# PulseChord.net
KiCad netlist of a schematic drawn in EAGLE
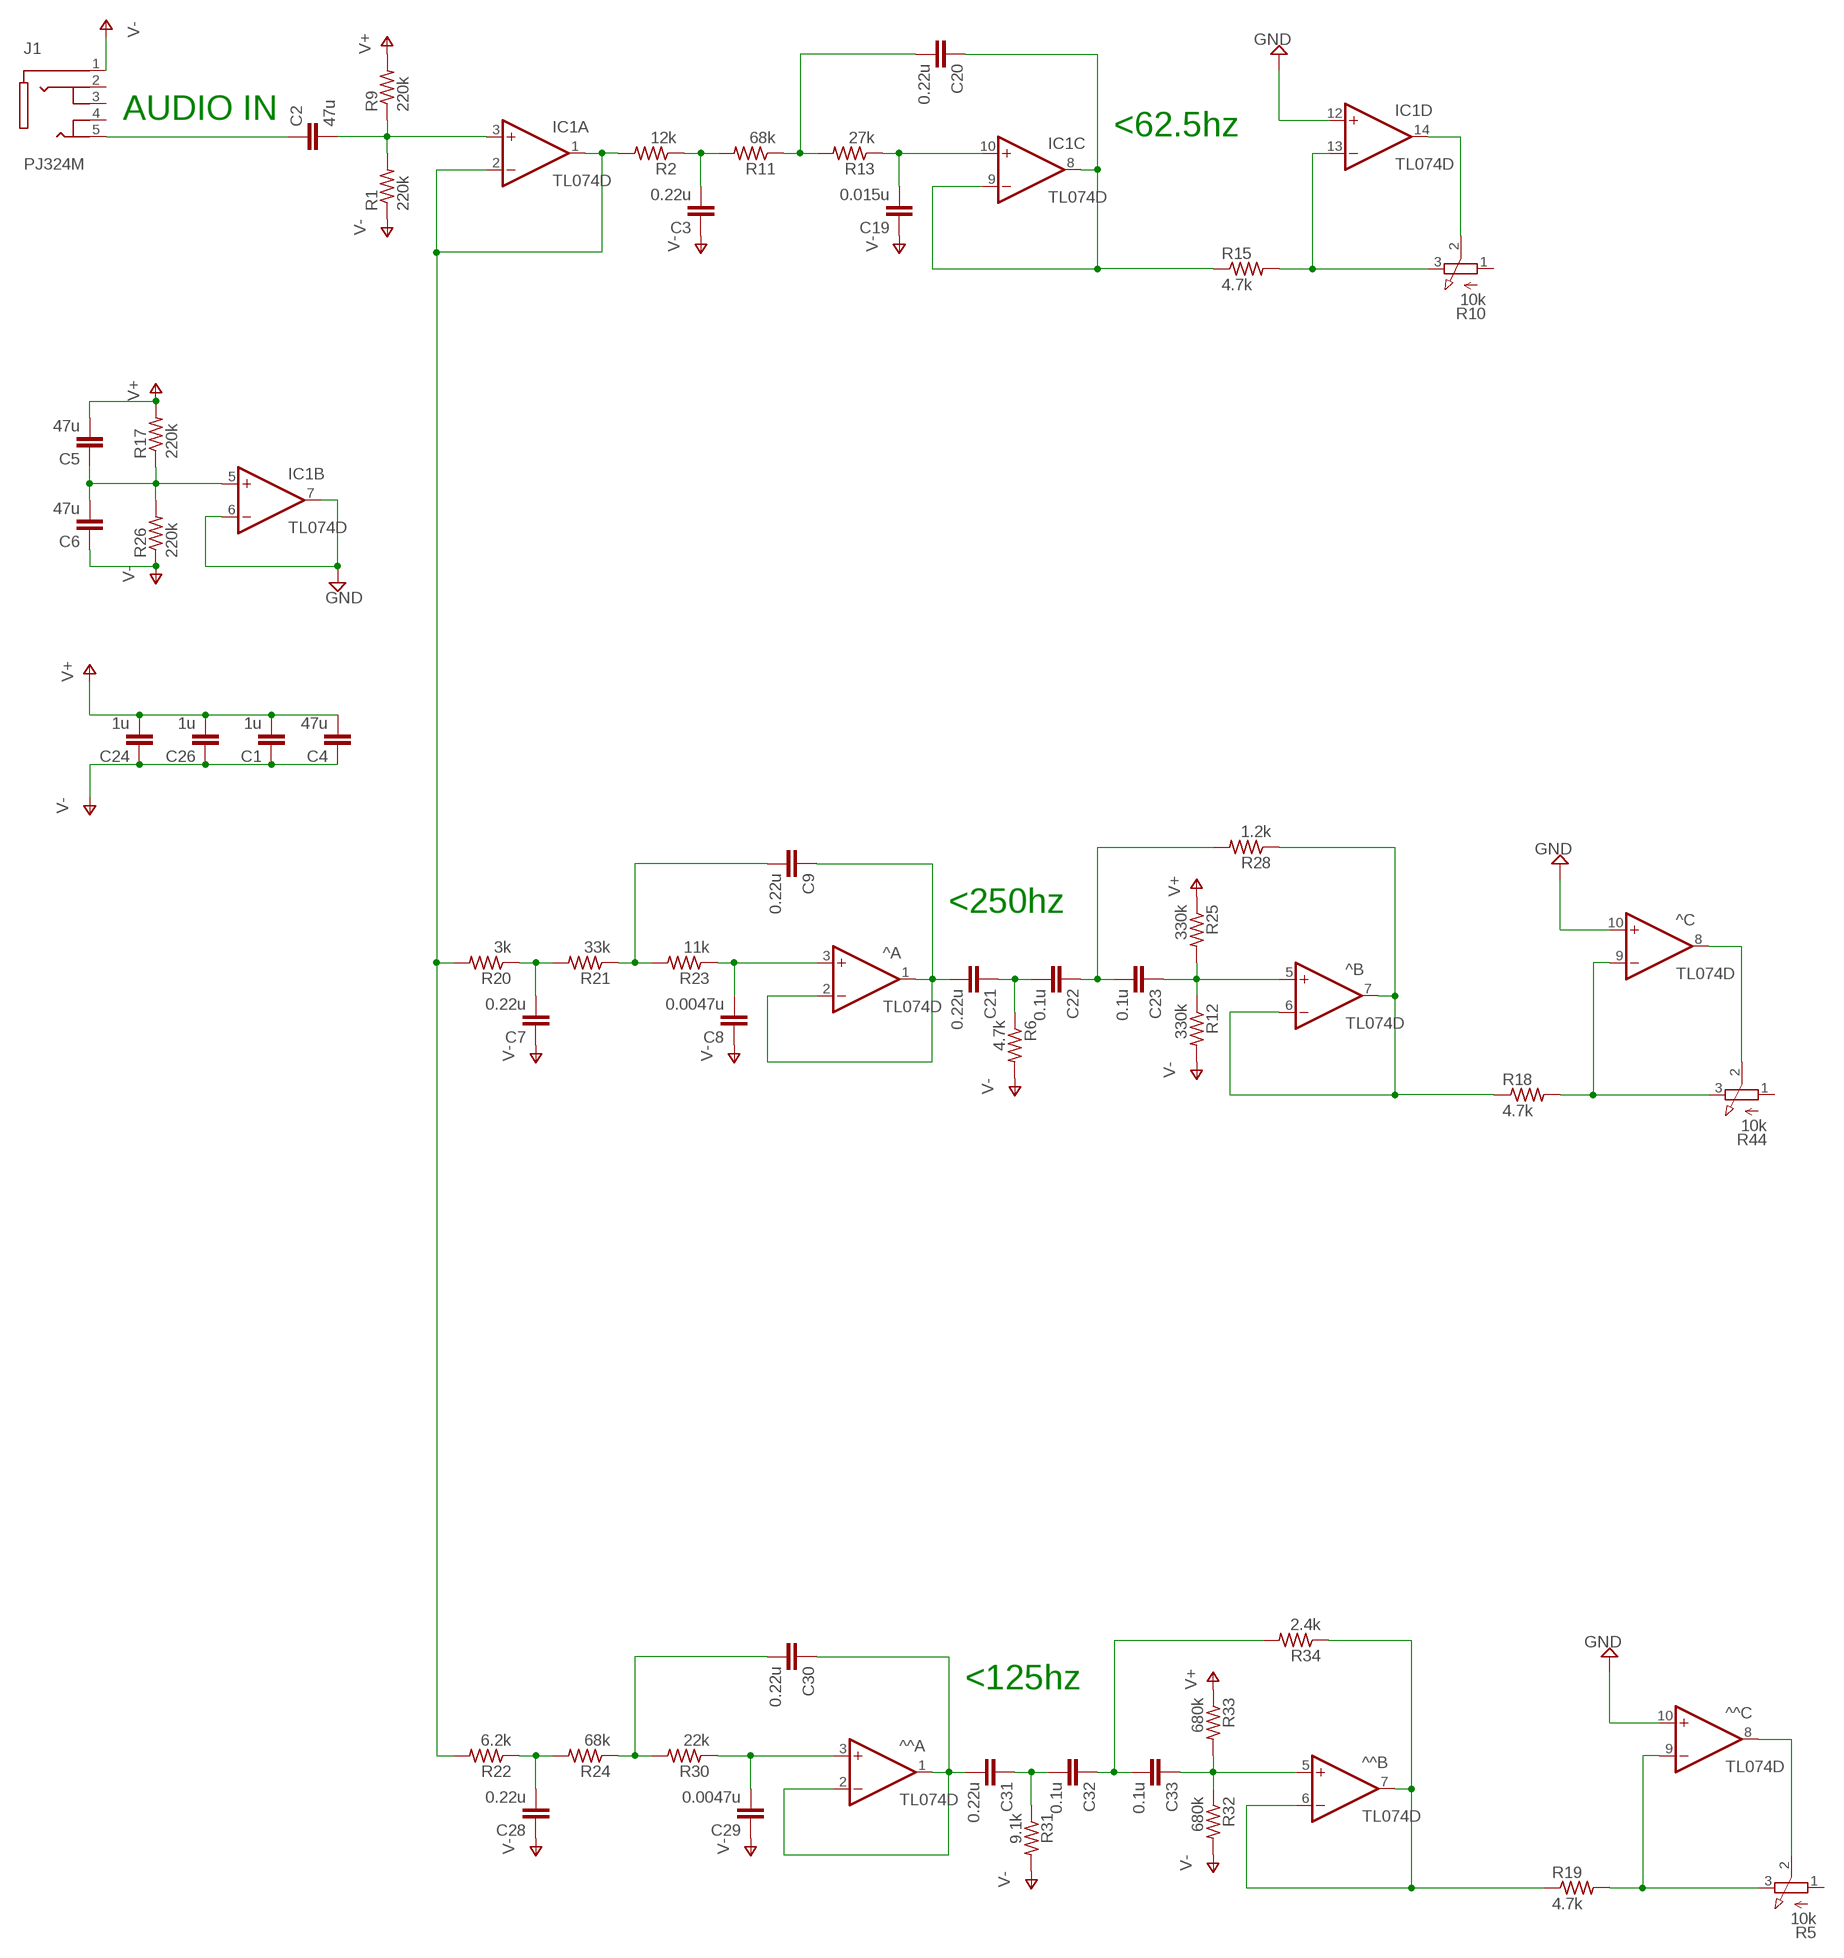
[diagram p0: schematic, sheet 1]

(export (version "E")
  (design (tool "Eeschema 10.0.6"))
  (components
    (comp (ref "C1")
      (value "1u")
      (footprint "eagle-import:C0603")
      (libsource (lib "eagle-import") (part "C-EUC0603"))
    )
    (comp (ref "C2")
      (value "47u")
      (footprint "eagle-import:C0603")
      (libsource (lib "eagle-import") (part "C-EUC0603"))
    )
    (comp (ref "C3")
      (value "0.22u")
      (footprint "eagle-import:C0603")
      (libsource (lib "eagle-import") (part "C-EUC0603"))
    )
    (comp (ref "C4")
      (value "47u")
      (footprint "eagle-import:C0603")
      (libsource (lib "eagle-import") (part "C-EUC0603"))
    )
    (comp (ref "C5")
      (value "47u")
      (footprint "eagle-import:C0603")
      (libsource (lib "eagle-import") (part "C-EUC0603"))
    )
    (comp (ref "C6")
      (value "47u")
      (footprint "eagle-import:C0603")
      (libsource (lib "eagle-import") (part "C-EUC0603"))
    )
    (comp (ref "C7")
      (value "0.22u")
      (footprint "eagle-import:C0603")
      (libsource (lib "eagle-import") (part "C-EUC0603"))
    )
    (comp (ref "C8")
      (value "0.0047u")
      (footprint "eagle-import:C0603")
      (libsource (lib "eagle-import") (part "C-EUC0603"))
    )
    (comp (ref "C9")
      (value "0.22u")
      (footprint "eagle-import:C0603")
      (libsource (lib "eagle-import") (part "C-EUC0603"))
    )
    (comp (ref "C19")
      (value "0.015u")
      (footprint "eagle-import:C0603")
      (libsource (lib "eagle-import") (part "C-EUC0603"))
    )
    (comp (ref "C20")
      (value "0.22u")
      (footprint "eagle-import:C0603")
      (libsource (lib "eagle-import") (part "C-EUC0603"))
    )
    (comp (ref "C21")
      (value "0.22u")
      (footprint "eagle-import:C0603")
      (libsource (lib "eagle-import") (part "C-EUC0603"))
    )
    (comp (ref "C22")
      (value "0.1u")
      (footprint "eagle-import:C0603")
      (libsource (lib "eagle-import") (part "C-EUC0603"))
    )
    (comp (ref "C23")
      (value "0.1u")
      (footprint "eagle-import:C0603")
      (libsource (lib "eagle-import") (part "C-EUC0603"))
    )
    (comp (ref "C24")
      (value "1u")
      (footprint "eagle-import:C0603")
      (libsource (lib "eagle-import") (part "C-EUC0603"))
    )
    (comp (ref "C26")
      (value "1u")
      (footprint "eagle-import:C0603")
      (libsource (lib "eagle-import") (part "C-EUC0603"))
    )
    (comp (ref "C28")
      (value "0.22u")
      (footprint "eagle-import:C0603")
      (libsource (lib "eagle-import") (part "C-EUC0603"))
    )
    (comp (ref "C29")
      (value "0.0047u")
      (footprint "eagle-import:C0603")
      (libsource (lib "eagle-import") (part "C-EUC0603"))
    )
    (comp (ref "C30")
      (value "0.22u")
      (footprint "eagle-import:C0603")
      (libsource (lib "eagle-import") (part "C-EUC0603"))
    )
    (comp (ref "C31")
      (value "0.22u")
      (footprint "eagle-import:C0603")
      (libsource (lib "eagle-import") (part "C-EUC0603"))
    )
    (comp (ref "C32")
      (value "0.1u")
      (footprint "eagle-import:C0603")
      (libsource (lib "eagle-import") (part "C-EUC0603"))
    )
    (comp (ref "C33")
      (value "0.1u")
      (footprint "eagle-import:C0603")
      (libsource (lib "eagle-import") (part "C-EUC0603"))
    )
    (comp (ref "IC1")
      (value "TL074D")
      (footprint "eagle-import:SO14")
      (libsource (lib "eagle-import") (part "TL074D"))
    )
    (comp (ref "J1")
      (value "PJ324M")
      (footprint "eagle-import:WENZHOU_PJ324M")
      (fields (field (name "MF") "Wenzhou QingPu Electronics Co.Ltd"))
      (libsource (lib "eagle-import") (part "PJ324M"))
    )
    (comp (ref "R1")
      (value "220k")
      (footprint "eagle-import:R0603")
      (libsource (lib "eagle-import") (part "R-US_R0603"))
    )
    (comp (ref "R2")
      (value "12k")
      (footprint "eagle-import:R0603")
      (libsource (lib "eagle-import") (part "R-US_R0603"))
    )
    (comp (ref "R5")
      (value "10k")
      (footprint "eagle-import:3RP_1610N")
      (libsource (lib "eagle-import") (part "3RP/1610N"))
    )
    (comp (ref "R6")
      (value "4.7k")
      (footprint "eagle-import:R0603")
      (libsource (lib "eagle-import") (part "R-US_R0603"))
    )
    (comp (ref "R9")
      (value "220k")
      (footprint "eagle-import:R0603")
      (libsource (lib "eagle-import") (part "R-US_R0603"))
    )
    (comp (ref "R10")
      (value "10k")
      (footprint "eagle-import:3RP_1610N")
      (libsource (lib "eagle-import") (part "3RP/1610N"))
    )
    (comp (ref "R11")
      (value "68k")
      (footprint "eagle-import:R0603")
      (libsource (lib "eagle-import") (part "R-US_R0603"))
    )
    (comp (ref "R12")
      (value "330k")
      (footprint "eagle-import:R0603")
      (libsource (lib "eagle-import") (part "R-US_R0603"))
    )
    (comp (ref "R13")
      (value "27k")
      (footprint "eagle-import:R0603")
      (libsource (lib "eagle-import") (part "R-US_R0603"))
    )
    (comp (ref "R15")
      (value "4.7k")
      (footprint "eagle-import:R0603")
      (libsource (lib "eagle-import") (part "R-US_R0603"))
    )
    (comp (ref "R17")
      (value "220k")
      (footprint "eagle-import:R0603")
      (libsource (lib "eagle-import") (part "R-US_R0603"))
    )
    (comp (ref "R18")
      (value "4.7k")
      (footprint "eagle-import:R0603")
      (libsource (lib "eagle-import") (part "R-US_R0603"))
    )
    (comp (ref "R19")
      (value "4.7k")
      (footprint "eagle-import:R0603")
      (libsource (lib "eagle-import") (part "R-US_R0603"))
    )
    (comp (ref "R20")
      (value "3k")
      (footprint "eagle-import:R0603")
      (libsource (lib "eagle-import") (part "R-US_R0603"))
    )
    (comp (ref "R21")
      (value "33k")
      (footprint "eagle-import:R0603")
      (libsource (lib "eagle-import") (part "R-US_R0603"))
    )
    (comp (ref "R22")
      (value "6.2k")
      (footprint "eagle-import:R0603")
      (libsource (lib "eagle-import") (part "R-US_R0603"))
    )
    (comp (ref "R23")
      (value "11k")
      (footprint "eagle-import:R0603")
      (libsource (lib "eagle-import") (part "R-US_R0603"))
    )
    (comp (ref "R24")
      (value "68k")
      (footprint "eagle-import:R0603")
      (libsource (lib "eagle-import") (part "R-US_R0603"))
    )
    (comp (ref "R25")
      (value "330k")
      (footprint "eagle-import:R0603")
      (libsource (lib "eagle-import") (part "R-US_R0603"))
    )
    (comp (ref "R26")
      (value "220k")
      (footprint "eagle-import:R0603")
      (libsource (lib "eagle-import") (part "R-US_R0603"))
    )
    (comp (ref "R28")
      (value "1.2k")
      (footprint "eagle-import:R0603")
      (libsource (lib "eagle-import") (part "R-US_R0603"))
    )
    (comp (ref "R30")
      (value "22k")
      (footprint "eagle-import:R0603")
      (libsource (lib "eagle-import") (part "R-US_R0603"))
    )
    (comp (ref "R31")
      (value "9.1k")
      (footprint "eagle-import:R0603")
      (libsource (lib "eagle-import") (part "R-US_R0603"))
    )
    (comp (ref "R32")
      (value "680k")
      (footprint "eagle-import:R0603")
      (libsource (lib "eagle-import") (part "R-US_R0603"))
    )
    (comp (ref "R33")
      (value "680k")
      (footprint "eagle-import:R0603")
      (libsource (lib "eagle-import") (part "R-US_R0603"))
    )
    (comp (ref "R34")
      (value "2.4k")
      (footprint "eagle-import:R0603")
      (libsource (lib "eagle-import") (part "R-US_R0603"))
    )
    (comp (ref "R44")
      (value "10k")
      (footprint "eagle-import:3RP_1610N")
      (libsource (lib "eagle-import") (part "3RP/1610N"))
    )
    (comp (ref "^")
      (value "TL074D")
      (footprint "eagle-import:SO14")
      (libsource (lib "eagle-import") (part "TL074D"))
    )
    (comp (ref "^^")
      (value "TL074D")
      (footprint "eagle-import:SO14")
      (libsource (lib "eagle-import") (part "TL074D"))
    )
  )
  (nets
    (net (code "1") (name "GND") (class "Default")
      (node (ref "IC1") (pin "12") (pinfunction "+IN_12") (pintype "input"))
      (node (ref "IC1") (pin "6") (pinfunction "-IN_6") (pintype "input"))
      (node (ref "IC1") (pin "7") (pinfunction "OUT_7") (pintype "output"))
      (node (ref "^") (pin "10") (pinfunction "+IN_10") (pintype "input"))
      (node (ref "^^") (pin "10") (pinfunction "+IN_10") (pintype "input"))
    )
    (net (code "2") (name "Net-(C3-Pad2)") (class "Default")
      (node (ref "C3") (pin "2") (pinfunction "2_2") (pintype "passive"))
      (node (ref "R11") (pin "2") (pinfunction "2_2") (pintype "passive"))
      (node (ref "R2") (pin "1") (pinfunction "1_1") (pintype "passive"))
    )
    (net (code "3") (name "Net-(C7-Pad2)") (class "Default")
      (node (ref "C7") (pin "2") (pinfunction "2_2") (pintype "passive"))
      (node (ref "R20") (pin "1") (pinfunction "1_1") (pintype "passive"))
      (node (ref "R21") (pin "2") (pinfunction "2_2") (pintype "passive"))
    )
    (net (code "4") (name "Net-(C9-Pad2)") (class "Default")
      (node (ref "C9") (pin "2") (pinfunction "2_2") (pintype "passive"))
      (node (ref "R21") (pin "1") (pinfunction "1_1") (pintype "passive"))
      (node (ref "R23") (pin "2") (pinfunction "2_2") (pintype "passive"))
    )
    (net (code "5") (name "Net-(C20-Pad2)") (class "Default")
      (node (ref "C20") (pin "2") (pinfunction "2_2") (pintype "passive"))
      (node (ref "R11") (pin "1") (pinfunction "1_1") (pintype "passive"))
      (node (ref "R13") (pin "2") (pinfunction "2_2") (pintype "passive"))
    )
    (net (code "6") (name "Net-(C21-Pad1)") (class "Default")
      (node (ref "C21") (pin "1") (pinfunction "1_1") (pintype "passive"))
      (node (ref "C22") (pin "2") (pinfunction "2_2") (pintype "passive"))
      (node (ref "R6") (pin "1") (pinfunction "1_1") (pintype "passive"))
    )
    (net (code "7") (name "Net-(C22-Pad1)") (class "Default")
      (node (ref "C22") (pin "1") (pinfunction "1_1") (pintype "passive"))
      (node (ref "C23") (pin "2") (pinfunction "2_2") (pintype "passive"))
      (node (ref "R28") (pin "2") (pinfunction "2_2") (pintype "passive"))
    )
    (net (code "8") (name "Net-(C28-Pad2)") (class "Default")
      (node (ref "C28") (pin "2") (pinfunction "2_2") (pintype "passive"))
      (node (ref "R22") (pin "1") (pinfunction "1_1") (pintype "passive"))
      (node (ref "R24") (pin "2") (pinfunction "2_2") (pintype "passive"))
    )
    (net (code "9") (name "Net-(C30-Pad2)") (class "Default")
      (node (ref "C30") (pin "2") (pinfunction "2_2") (pintype "passive"))
      (node (ref "R24") (pin "1") (pinfunction "1_1") (pintype "passive"))
      (node (ref "R30") (pin "2") (pinfunction "2_2") (pintype "passive"))
    )
    (net (code "10") (name "Net-(C31-Pad1)") (class "Default")
      (node (ref "C31") (pin "1") (pinfunction "1_1") (pintype "passive"))
      (node (ref "C32") (pin "2") (pinfunction "2_2") (pintype "passive"))
      (node (ref "R31") (pin "1") (pinfunction "1_1") (pintype "passive"))
    )
    (net (code "11") (name "Net-(C32-Pad1)") (class "Default")
      (node (ref "C32") (pin "1") (pinfunction "1_1") (pintype "passive"))
      (node (ref "C33") (pin "2") (pinfunction "2_2") (pintype "passive"))
      (node (ref "R34") (pin "2") (pinfunction "2_2") (pintype "passive"))
    )
    (net (code "12") (name "Net-(IC1A-+IN)") (class "Default")
      (node (ref "C2") (pin "2") (pinfunction "2_2") (pintype "passive"))
      (node (ref "IC1") (pin "3") (pinfunction "+IN_3") (pintype "input"))
      (node (ref "R1") (pin "2") (pinfunction "2_2") (pintype "passive"))
      (node (ref "R9") (pin "1") (pinfunction "1_1") (pintype "passive"))
    )
    (net (code "13") (name "Net-(IC1A--IN)") (class "Default")
      (node (ref "IC1") (pin "1") (pinfunction "OUT_1") (pintype "output"))
      (node (ref "IC1") (pin "2") (pinfunction "-IN_2") (pintype "input"))
      (node (ref "R2") (pin "2") (pinfunction "2_2") (pintype "passive"))
      (node (ref "R20") (pin "2") (pinfunction "2_2") (pintype "passive"))
      (node (ref "R22") (pin "2") (pinfunction "2_2") (pintype "passive"))
    )
    (net (code "14") (name "Net-(IC1B-+IN)") (class "Default")
      (node (ref "C5") (pin "1") (pinfunction "1_1") (pintype "passive"))
      (node (ref "C6") (pin "2") (pinfunction "2_2") (pintype "passive"))
      (node (ref "IC1") (pin "5") (pinfunction "+IN_5") (pintype "input"))
      (node (ref "R17") (pin "1") (pinfunction "1_1") (pintype "passive"))
      (node (ref "R26") (pin "2") (pinfunction "2_2") (pintype "passive"))
    )
    (net (code "15") (name "Net-(IC1C-+IN)") (class "Default")
      (node (ref "C19") (pin "2") (pinfunction "2_2") (pintype "passive"))
      (node (ref "IC1") (pin "10") (pinfunction "+IN_10") (pintype "input"))
      (node (ref "R13") (pin "1") (pinfunction "1_1") (pintype "passive"))
    )
    (net (code "16") (name "Net-(IC1C--IN)") (class "Default")
      (node (ref "C20") (pin "1") (pinfunction "1_1") (pintype "passive"))
      (node (ref "IC1") (pin "8") (pinfunction "OUT_8") (pintype "output"))
      (node (ref "IC1") (pin "9") (pinfunction "-IN_9") (pintype "input"))
      (node (ref "R15") (pin "1") (pinfunction "1_1") (pintype "passive"))
    )
    (net (code "17") (name "Net-(IC1D--IN)") (class "Default")
      (node (ref "IC1") (pin "13") (pinfunction "-IN_13") (pintype "input"))
      (node (ref "R10") (pin "3") (pinfunction "E_3") (pintype "passive"))
      (node (ref "R15") (pin "2") (pinfunction "2_2") (pintype "passive"))
    )
    (net (code "18") (name "Net-(IC1D-OUT)") (class "Default")
      (node (ref "IC1") (pin "14") (pinfunction "OUT_14") (pintype "output"))
      (node (ref "R10") (pin "2") (pinfunction "S_2") (pintype "passive"))
    )
    (net (code "19") (name "Net-(J1-TIP_2)") (class "Default")
      (node (ref "C2") (pin "1") (pinfunction "1_1") (pintype "passive"))
      (node (ref "J1") (pin "5") (pinfunction "TIP_2_5") (pintype "passive"))
    )
    (net (code "20") (name "Net-(R5-E)") (class "Default")
      (node (ref "R19") (pin "2") (pinfunction "2_2") (pintype "passive"))
      (node (ref "R5") (pin "3") (pinfunction "E_3") (pintype "passive"))
      (node (ref "^^") (pin "9") (pinfunction "-IN_9") (pintype "input"))
    )
    (net (code "21") (name "Net-(R5-S)") (class "Default")
      (node (ref "R5") (pin "2") (pinfunction "S_2") (pintype "passive"))
      (node (ref "^^") (pin "8") (pinfunction "OUT_8") (pintype "output"))
    )
    (net (code "22") (name "Net-(R44-E)") (class "Default")
      (node (ref "R18") (pin "2") (pinfunction "2_2") (pintype "passive"))
      (node (ref "R44") (pin "3") (pinfunction "E_3") (pintype "passive"))
      (node (ref "^") (pin "9") (pinfunction "-IN_9") (pintype "input"))
    )
    (net (code "23") (name "Net-(R44-S)") (class "Default")
      (node (ref "R44") (pin "2") (pinfunction "S_2") (pintype "passive"))
      (node (ref "^") (pin "8") (pinfunction "OUT_8") (pintype "output"))
    )
    (net (code "24") (name "Net-(^A-+IN)") (class "Default")
      (node (ref "C8") (pin "2") (pinfunction "2_2") (pintype "passive"))
      (node (ref "R23") (pin "1") (pinfunction "1_1") (pintype "passive"))
      (node (ref "^") (pin "3") (pinfunction "+IN_3") (pintype "input"))
    )
    (net (code "25") (name "Net-(^A--IN)") (class "Default")
      (node (ref "C21") (pin "2") (pinfunction "2_2") (pintype "passive"))
      (node (ref "C9") (pin "1") (pinfunction "1_1") (pintype "passive"))
      (node (ref "^") (pin "1") (pinfunction "OUT_1") (pintype "output"))
      (node (ref "^") (pin "2") (pinfunction "-IN_2") (pintype "input"))
    )
    (net (code "26") (name "Net-(^B-+IN)") (class "Default")
      (node (ref "C23") (pin "1") (pinfunction "1_1") (pintype "passive"))
      (node (ref "R12") (pin "1") (pinfunction "1_1") (pintype "passive"))
      (node (ref "R25") (pin "2") (pinfunction "2_2") (pintype "passive"))
      (node (ref "^") (pin "5") (pinfunction "+IN_5") (pintype "input"))
    )
    (net (code "27") (name "Net-(^B--IN)") (class "Default")
      (node (ref "R18") (pin "1") (pinfunction "1_1") (pintype "passive"))
      (node (ref "R28") (pin "1") (pinfunction "1_1") (pintype "passive"))
      (node (ref "^") (pin "6") (pinfunction "-IN_6") (pintype "input"))
      (node (ref "^") (pin "7") (pinfunction "OUT_7") (pintype "output"))
    )
    (net (code "28") (name "Net-(^^A-+IN)") (class "Default")
      (node (ref "C29") (pin "2") (pinfunction "2_2") (pintype "passive"))
      (node (ref "R30") (pin "1") (pinfunction "1_1") (pintype "passive"))
      (node (ref "^^") (pin "3") (pinfunction "+IN_3") (pintype "input"))
    )
    (net (code "29") (name "Net-(^^A--IN)") (class "Default")
      (node (ref "C30") (pin "1") (pinfunction "1_1") (pintype "passive"))
      (node (ref "C31") (pin "2") (pinfunction "2_2") (pintype "passive"))
      (node (ref "^^") (pin "1") (pinfunction "OUT_1") (pintype "output"))
      (node (ref "^^") (pin "2") (pinfunction "-IN_2") (pintype "input"))
    )
    (net (code "30") (name "Net-(^^B-+IN)") (class "Default")
      (node (ref "C33") (pin "1") (pinfunction "1_1") (pintype "passive"))
      (node (ref "R32") (pin "1") (pinfunction "1_1") (pintype "passive"))
      (node (ref "R33") (pin "2") (pinfunction "2_2") (pintype "passive"))
      (node (ref "^^") (pin "5") (pinfunction "+IN_5") (pintype "input"))
    )
    (net (code "31") (name "Net-(^^B--IN)") (class "Default")
      (node (ref "R19") (pin "1") (pinfunction "1_1") (pintype "passive"))
      (node (ref "R34") (pin "1") (pinfunction "1_1") (pintype "passive"))
      (node (ref "^^") (pin "6") (pinfunction "-IN_6") (pintype "input"))
      (node (ref "^^") (pin "7") (pinfunction "OUT_7") (pintype "output"))
    )
    (net (code "32") (name "V+") (class "Default")
      (node (ref "C1") (pin "2") (pinfunction "2_2") (pintype "passive"))
      (node (ref "C24") (pin "2") (pinfunction "2_2") (pintype "passive"))
      (node (ref "C26") (pin "2") (pinfunction "2_2") (pintype "passive"))
      (node (ref "C4") (pin "2") (pinfunction "2_2") (pintype "passive"))
      (node (ref "C5") (pin "2") (pinfunction "2_2") (pintype "passive"))
      (node (ref "R17") (pin "2") (pinfunction "2_2") (pintype "passive"))
      (node (ref "R25") (pin "1") (pinfunction "1_1") (pintype "passive"))
      (node (ref "R33") (pin "1") (pinfunction "1_1") (pintype "passive"))
      (node (ref "R9") (pin "2") (pinfunction "2_2") (pintype "passive"))
    )
    (net (code "33") (name "V-") (class "Default")
      (node (ref "C1") (pin "1") (pinfunction "1_1") (pintype "passive"))
      (node (ref "C19") (pin "1") (pinfunction "1_1") (pintype "passive"))
      (node (ref "C24") (pin "1") (pinfunction "1_1") (pintype "passive"))
      (node (ref "C26") (pin "1") (pinfunction "1_1") (pintype "passive"))
      (node (ref "C28") (pin "1") (pinfunction "1_1") (pintype "passive"))
      (node (ref "C29") (pin "1") (pinfunction "1_1") (pintype "passive"))
      (node (ref "C3") (pin "1") (pinfunction "1_1") (pintype "passive"))
      (node (ref "C4") (pin "1") (pinfunction "1_1") (pintype "passive"))
      (node (ref "C6") (pin "1") (pinfunction "1_1") (pintype "passive"))
      (node (ref "C7") (pin "1") (pinfunction "1_1") (pintype "passive"))
      (node (ref "C8") (pin "1") (pinfunction "1_1") (pintype "passive"))
      (node (ref "J1") (pin "1") (pinfunction "SLEEVE_1") (pintype "passive"))
      (node (ref "R1") (pin "1") (pinfunction "1_1") (pintype "passive"))
      (node (ref "R12") (pin "2") (pinfunction "2_2") (pintype "passive"))
      (node (ref "R26") (pin "1") (pinfunction "1_1") (pintype "passive"))
      (node (ref "R31") (pin "2") (pinfunction "2_2") (pintype "passive"))
      (node (ref "R32") (pin "2") (pinfunction "2_2") (pintype "passive"))
      (node (ref "R6") (pin "2") (pinfunction "2_2") (pintype "passive"))
    )
    (net (code "34") (name "unconnected-(J1-RING_1-Pad2)") (class "Default")
      (node (ref "J1") (pin "2") (pinfunction "RING_1_2") (pintype "passive"))
    )
    (net (code "35") (name "unconnected-(J1-RING_2-Pad3)") (class "Default")
      (node (ref "J1") (pin "3") (pinfunction "RING_2_3") (pintype "passive"))
    )
    (net (code "36") (name "unconnected-(J1-TIP_1-Pad4)") (class "Default")
      (node (ref "J1") (pin "4") (pinfunction "TIP_1_4") (pintype "passive"))
    )
    (net (code "37") (name "unconnected-(R5-A-Pad1)") (class "Default")
      (node (ref "R5") (pin "1") (pinfunction "A_1") (pintype "passive"))
    )
    (net (code "38") (name "unconnected-(R10-A-Pad1)") (class "Default")
      (node (ref "R10") (pin "1") (pinfunction "A_1") (pintype "passive"))
    )
    (net (code "39") (name "unconnected-(R44-A-Pad1)") (class "Default")
      (node (ref "R44") (pin "1") (pinfunction "A_1") (pintype "passive"))
    )
  )
)
